# pc_healthypi_move_sensor_dual_v2.net
KiCad netlist of a schematic drawn in EAGLE
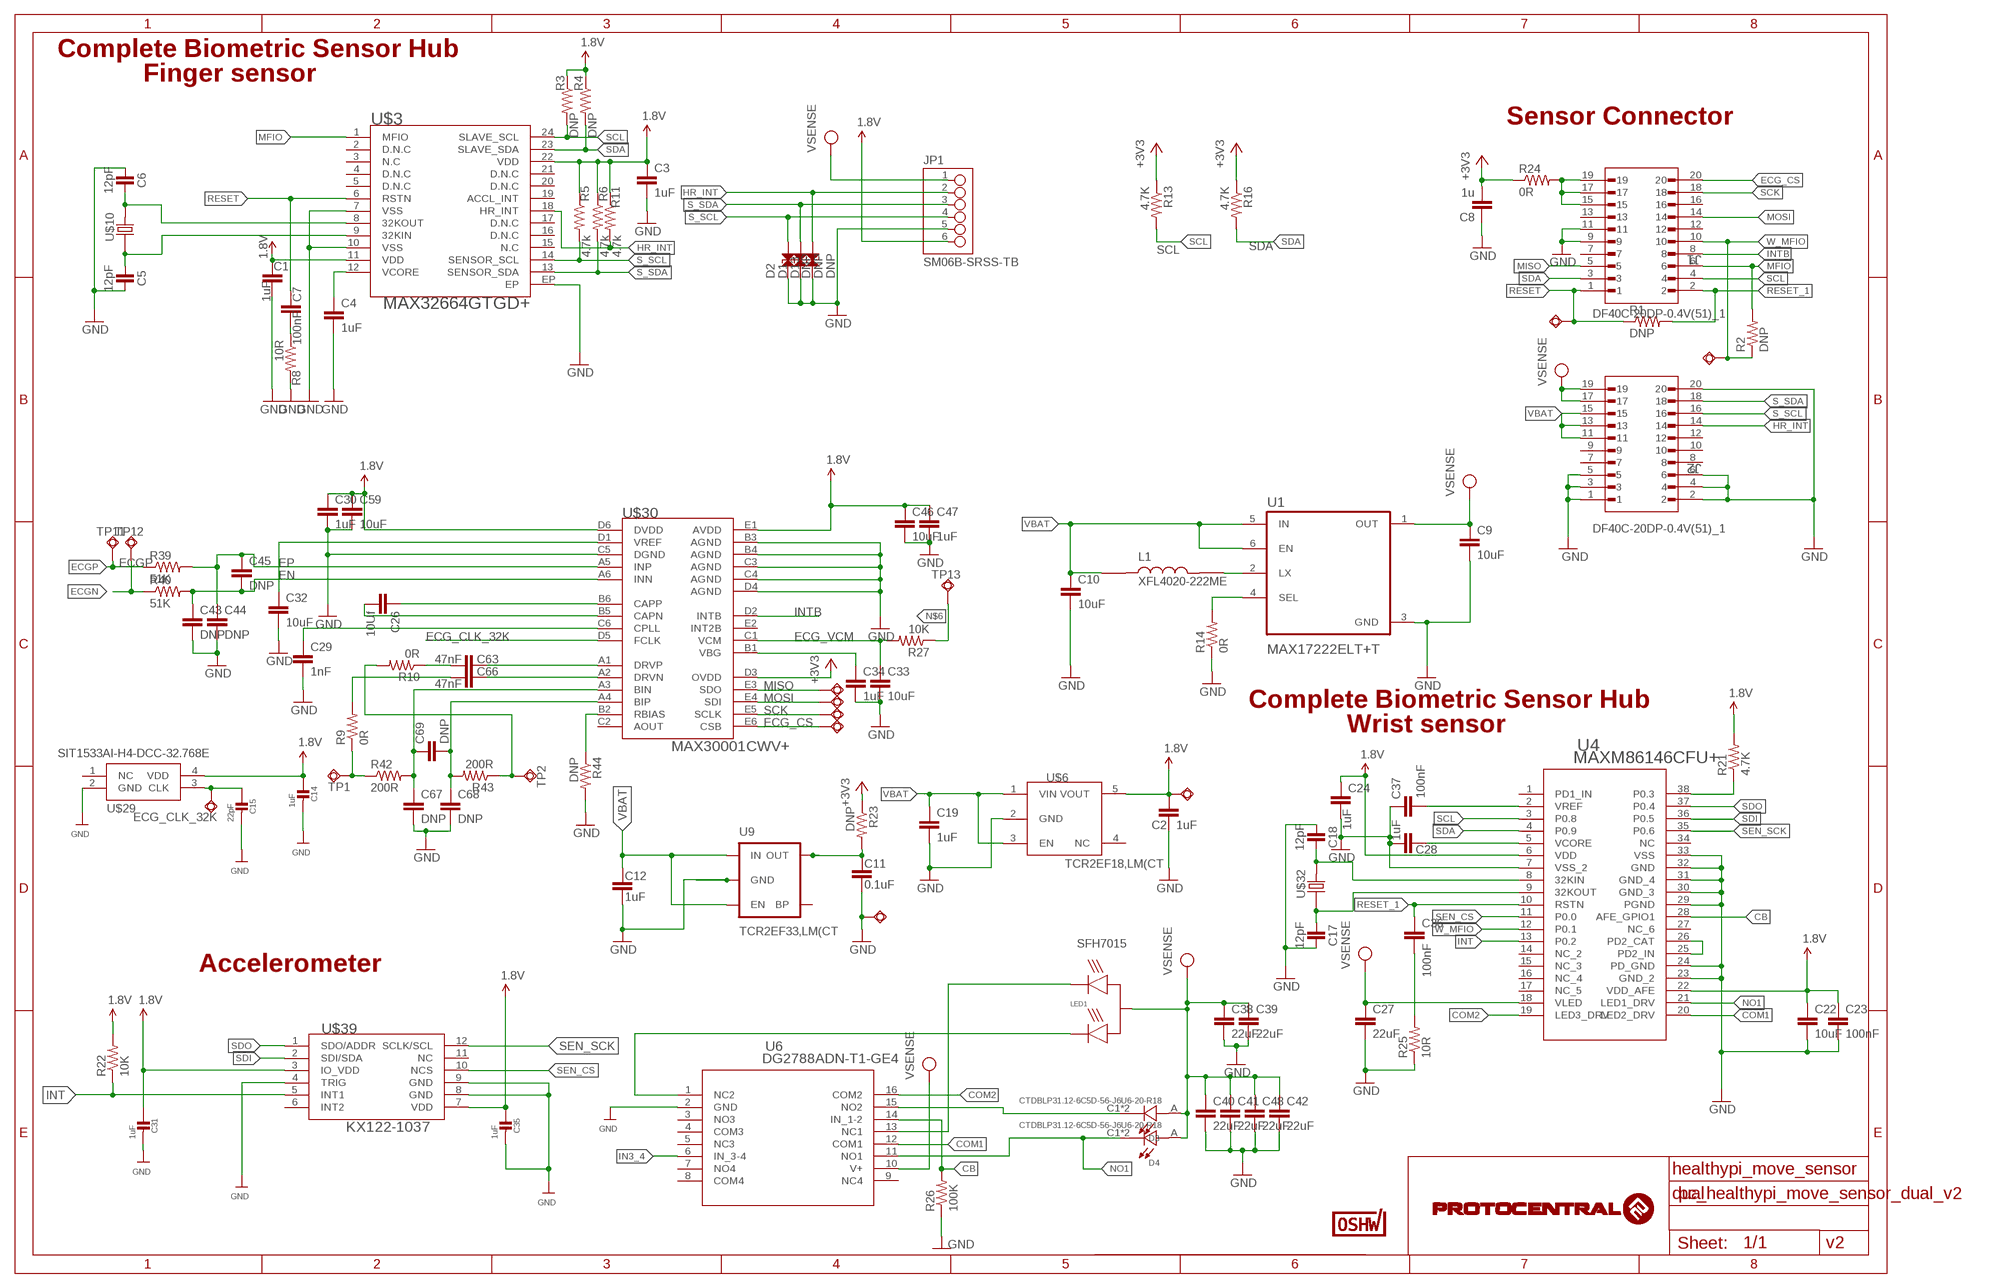
[diagram p0: schematic, sheet 1]

(export (version "E")
  (design (tool "Eeschema 10.0.6"))
  (components
    (comp (ref "C1")
      (value "1uF")
      (footprint "eagle-import:C0402")
      (libsource (lib "eagle-import") (part "C-EUC0402"))
    )
    (comp (ref "C2")
      (value "1uF")
      (footprint "eagle-import:C0402")
      (libsource (lib "eagle-import") (part "C-EUC0402"))
    )
    (comp (ref "C3")
      (value "1uF")
      (footprint "eagle-import:C0402")
      (libsource (lib "eagle-import") (part "C-EUC0402"))
    )
    (comp (ref "C4")
      (value "1uF")
      (footprint "eagle-import:C0402")
      (libsource (lib "eagle-import") (part "C-EUC0402"))
    )
    (comp (ref "C5")
      (value "12pF")
      (footprint "eagle-import:C0402")
      (libsource (lib "eagle-import") (part "CAPACITORS-0402"))
    )
    (comp (ref "C6")
      (value "12pF")
      (footprint "eagle-import:C0402")
      (libsource (lib "eagle-import") (part "CAPACITORS-0402"))
    )
    (comp (ref "C7")
      (value "100nF")
      (footprint "eagle-import:C0402")
      (libsource (lib "eagle-import") (part "C-EUC0402"))
    )
    (comp (ref "C8")
      (value "1u")
      (footprint "eagle-import:C0402")
      (libsource (lib "eagle-import") (part "C-EUC0402"))
    )
    (comp (ref "C9")
      (value "10uF")
      (footprint "eagle-import:C0402")
      (libsource (lib "eagle-import") (part "C-EUC0402"))
    )
    (comp (ref "C10")
      (value "10uF")
      (footprint "eagle-import:C0402")
      (libsource (lib "eagle-import") (part "C-EUC0402"))
    )
    (comp (ref "C11")
      (value "0.1uF")
      (footprint "eagle-import:0402")
      (libsource (lib "eagle-import") (part "0.1UF-0402-16V-10%"))
    )
    (comp (ref "C12")
      (value "1uF")
      (footprint "eagle-import:0402-TIGHT")
      (libsource (lib "eagle-import") (part "0.1UF-0402T-6.3V-10%-X7R"))
    )
    (comp (ref "C14")
      (value "1uF")
      (footprint "eagle-import:0402")
      (libsource (lib "eagle-import") (part "CAP_CERAMIC0402"))
    )
    (comp (ref "C15")
      (value "22pF")
      (footprint "eagle-import:0402")
      (libsource (lib "eagle-import") (part "CAP_CERAMIC0402"))
    )
    (comp (ref "C17")
      (value "12pF")
      (footprint "eagle-import:C0402")
      (libsource (lib "eagle-import") (part "CAPACITORS-0402"))
    )
    (comp (ref "C18")
      (value "12pF")
      (footprint "eagle-import:C0402")
      (libsource (lib "eagle-import") (part "CAPACITORS-0402"))
    )
    (comp (ref "C19")
      (value "1uF")
      (footprint "eagle-import:C0402")
      (libsource (lib "eagle-import") (part "C-EUC0402"))
    )
    (comp (ref "C22")
      (value "10uF")
      (footprint "eagle-import:C0402")
      (libsource (lib "eagle-import") (part "C-EUC0402"))
    )
    (comp (ref "C23")
      (value "100nF")
      (footprint "eagle-import:C0402")
      (libsource (lib "eagle-import") (part "C-EUC0402"))
    )
    (comp (ref "C24")
      (value "1uF")
      (footprint "eagle-import:C0402")
      (libsource (lib "eagle-import") (part "C-EUC0402"))
    )
    (comp (ref "C26")
      (value "10Uf")
      (footprint "eagle-import:C0402")
      (libsource (lib "eagle-import") (part "C-EUC0402"))
    )
    (comp (ref "C27")
      (value "22uF")
      (footprint "eagle-import:C0805")
      (libsource (lib "eagle-import") (part "C-EUC0805"))
    )
    (comp (ref "C28")
      (value "1uF")
      (footprint "eagle-import:C0402")
      (libsource (lib "eagle-import") (part "C-EUC0402"))
    )
    (comp (ref "C29")
      (value "1nF")
      (footprint "eagle-import:C0402")
      (libsource (lib "eagle-import") (part "C-EUC0402"))
    )
    (comp (ref "C30")
      (value "1uF")
      (footprint "eagle-import:C0402")
      (libsource (lib "eagle-import") (part "C-EUC0402"))
    )
    (comp (ref "C31")
      (value "1uF")
      (footprint "eagle-import:0402")
      (libsource (lib "eagle-import") (part "CAP_CERAMIC0402"))
    )
    (comp (ref "C32")
      (value "10uF")
      (footprint "eagle-import:C0402")
      (libsource (lib "eagle-import") (part "C-EUC0402"))
    )
    (comp (ref "C33")
      (value "10uF")
      (footprint "eagle-import:C0402")
      (libsource (lib "eagle-import") (part "C-EUC0402"))
    )
    (comp (ref "C34")
      (value "1uF")
      (footprint "eagle-import:C0402")
      (libsource (lib "eagle-import") (part "C-EUC0402"))
    )
    (comp (ref "C35")
      (value "1uF")
      (footprint "eagle-import:0402")
      (libsource (lib "eagle-import") (part "CAP_CERAMIC0402"))
    )
    (comp (ref "C36")
      (value "100nF")
      (footprint "eagle-import:C0402")
      (libsource (lib "eagle-import") (part "C-EUC0402"))
    )
    (comp (ref "C37")
      (value "100nF")
      (footprint "eagle-import:C0402")
      (libsource (lib "eagle-import") (part "C-EUC0402"))
    )
    (comp (ref "C38")
      (value "22uF")
      (footprint "eagle-import:C0805")
      (libsource (lib "eagle-import") (part "C-EUC0805"))
    )
    (comp (ref "C39")
      (value "22uF")
      (footprint "eagle-import:C0805")
      (libsource (lib "eagle-import") (part "C-EUC0805"))
    )
    (comp (ref "C40")
      (value "22uF")
      (footprint "eagle-import:C0805")
      (libsource (lib "eagle-import") (part "C-EUC0805"))
    )
    (comp (ref "C41")
      (value "22uF")
      (footprint "eagle-import:C0805")
      (libsource (lib "eagle-import") (part "C-EUC0805"))
    )
    (comp (ref "C42")
      (value "22uF")
      (footprint "eagle-import:C0805")
      (libsource (lib "eagle-import") (part "C-EUC0805"))
    )
    (comp (ref "C43")
      (value "DNP")
      (footprint "eagle-import:C0402")
      (libsource (lib "eagle-import") (part "C-EUC0402"))
    )
    (comp (ref "C44")
      (value "DNP")
      (footprint "eagle-import:C0402")
      (libsource (lib "eagle-import") (part "C-EUC0402"))
    )
    (comp (ref "C45")
      (value "DNP")
      (footprint "eagle-import:C0402")
      (libsource (lib "eagle-import") (part "C-EUC0402"))
    )
    (comp (ref "C46")
      (value "10uF")
      (footprint "eagle-import:C0402")
      (libsource (lib "eagle-import") (part "C-EUC0402"))
    )
    (comp (ref "C47")
      (value "1uF")
      (footprint "eagle-import:C0402")
      (libsource (lib "eagle-import") (part "C-EUC0402"))
    )
    (comp (ref "C48")
      (value "22uF")
      (footprint "eagle-import:C0805")
      (libsource (lib "eagle-import") (part "C-EUC0805"))
    )
    (comp (ref "C59")
      (value "10uF")
      (footprint "eagle-import:C0402")
      (libsource (lib "eagle-import") (part "C-EUC0402"))
    )
    (comp (ref "C63")
      (value "47nF")
      (footprint "eagle-import:C0402")
      (libsource (lib "eagle-import") (part "C-EUC0402"))
    )
    (comp (ref "C66")
      (value "47nF")
      (footprint "eagle-import:C0402")
      (libsource (lib "eagle-import") (part "C-EUC0402"))
    )
    (comp (ref "C67")
      (value "DNP")
      (footprint "eagle-import:C0402")
      (libsource (lib "eagle-import") (part "C-EUC0402"))
    )
    (comp (ref "C68")
      (value "DNP")
      (footprint "eagle-import:C0402")
      (libsource (lib "eagle-import") (part "C-EUC0402"))
    )
    (comp (ref "C69")
      (value "DNP")
      (footprint "eagle-import:C0402")
      (libsource (lib "eagle-import") (part "C-EUC0402"))
    )
    (comp (ref "D1")
      (value "DNP")
      (footprint "eagle-import:0402")
      (fields
        (field (name "DIGIKEY_PART") "PESD0402-140CT-ND")
        (field (name "MOUSE_PART") "650-PESD0402-140")
      )
      (libsource (lib "eagle-import") (part "PESD0402-0402"))
    )
    (comp (ref "D2")
      (value "DNP")
      (footprint "eagle-import:0402")
      (fields
        (field (name "DIGIKEY_PART") "PESD0402-140CT-ND")
        (field (name "MOUSE_PART") "650-PESD0402-140")
      )
      (libsource (lib "eagle-import") (part "PESD0402-0402"))
    )
    (comp (ref "D3")
      (value "CTDBLP31.12-6C5D-56-J6U6-20-R18")
      (footprint "eagle-import:LED_CTDBLP31.12-6C5D-56-J6U6-20-R18")
      (fields
        (field (name "MF") "OSRAM Opto Semiconductors")
        (field (name "MP") "CT DBLP31.12-6C5D-56-J6U6-20-R18")
      )
      (libsource (lib "eagle-import") (part "CTDBLP31.12-6C5D-56-J6U6-20-R18"))
    )
    (comp (ref "D4")
      (value "CTDBLP31.12-6C5D-56-J6U6-20-R18")
      (footprint "eagle-import:LED_CTDBLP31.12-6C5D-56-J6U6-20-R18")
      (fields
        (field (name "MF") "OSRAM Opto Semiconductors")
        (field (name "MP") "CT DBLP31.12-6C5D-56-J6U6-20-R18")
      )
      (libsource (lib "eagle-import") (part "CTDBLP31.12-6C5D-56-J6U6-20-R18"))
    )
    (comp (ref "D13")
      (value "DNP")
      (footprint "eagle-import:0402")
      (fields
        (field (name "DIGIKEY_PART") "PESD0402-140CT-ND")
        (field (name "MOUSE_PART") "650-PESD0402-140")
      )
      (libsource (lib "eagle-import") (part "PESD0402-0402"))
    )
    (comp (ref "J1")
      (value "DF40C-20DP-0.4V(51)_1")
      (footprint "eagle-import:HRS_DF40C-20DP-0.4V(51)")
      (fields (field (name "MANUFACTURER") "Hirose Electric"))
      (libsource (lib "eagle-import") (part "DF40C-20DP-0.4V(51)_1"))
    )
    (comp (ref "J2")
      (value "DF40C-20DP-0.4V(51)_1")
      (footprint "eagle-import:HRS_DF40C-20DP-0.4V(51)")
      (fields (field (name "MANUFACTURER") "Hirose Electric"))
      (libsource (lib "eagle-import") (part "DF40C-20DP-0.4V(51)_1"))
    )
    (comp (ref "JP1")
      (value "SM06B-SRSS-TB")
      (footprint "eagle-import:SM06B-SRSS-TB")
      (fields (field (name "MF") "JST Sales"))
      (libsource (lib "eagle-import") (part "SM06B-SRSS-TB"))
    )
    (comp (ref "L1")
      (value "XFL4020-222ME")
      (footprint "eagle-import:IND_XFL4020-222ME")
      (fields (field (name "MF") "Coilcraft"))
      (libsource (lib "eagle-import") (part "XFL4020-222ME"))
    )
    (comp (ref "LED1")
      (value "SFH7015")
      (footprint "eagle-import:SFH7015")
      (fields (field (name "MF") "OSRAM Opto Semiconductors") (field (name "MP") "SFH 7015"))
      (libsource (lib "eagle-import") (part "SFH7015"))
    )
    (comp (ref "R1")
      (value "DNP")
      (footprint "eagle-import:0402-RES")
      (libsource (lib "eagle-import") (part "RESISTOR0402-RES"))
    )
    (comp (ref "R2")
      (value "DNP")
      (footprint "eagle-import:0402-RES")
      (libsource (lib "eagle-import") (part "RESISTOR0402-RES"))
    )
    (comp (ref "R3")
      (value "DNP")
      (footprint "eagle-import:0402-RES")
      (libsource (lib "eagle-import") (part "RESISTOR0402-RES"))
    )
    (comp (ref "R4")
      (value "DNP")
      (footprint "eagle-import:0402-RES")
      (libsource (lib "eagle-import") (part "RESISTOR0402-RES"))
    )
    (comp (ref "R5")
      (value "4.7k")
      (footprint "eagle-import:0402-RES")
      (libsource (lib "eagle-import") (part "RESISTOR0402-RES"))
    )
    (comp (ref "R6")
      (value "4.7k")
      (footprint "eagle-import:0402-RES")
      (libsource (lib "eagle-import") (part "RESISTOR0402-RES"))
    )
    (comp (ref "R8")
      (value "10R")
      (footprint "eagle-import:0402-RES")
      (libsource (lib "eagle-import") (part "RESISTOR0402-RES"))
    )
    (comp (ref "R9")
      (value "0R")
      (footprint "eagle-import:0402-RES")
      (libsource (lib "eagle-import") (part "RESISTOR0402-RES"))
    )
    (comp (ref "R10")
      (value "0R")
      (footprint "eagle-import:0402-RES")
      (libsource (lib "eagle-import") (part "RESISTOR0402-RES"))
    )
    (comp (ref "R11")
      (value "4.7k")
      (footprint "eagle-import:0402-RES")
      (libsource (lib "eagle-import") (part "RESISTOR0402-RES"))
    )
    (comp (ref "R13")
      (value "4.7K")
      (footprint "eagle-import:0402-RES")
      (libsource (lib "eagle-import") (part "RESISTOR0402-RES"))
    )
    (comp (ref "R14")
      (value "0R")
      (footprint "eagle-import:R0402")
      (libsource (lib "eagle-import") (part "R-US_R0402"))
    )
    (comp (ref "R16")
      (value "4.7K")
      (footprint "eagle-import:0402-RES")
      (libsource (lib "eagle-import") (part "RESISTOR0402-RES"))
    )
    (comp (ref "R21")
      (value "4.7K")
      (footprint "eagle-import:R0402")
      (libsource (lib "eagle-import") (part "R-US_R0402"))
    )
    (comp (ref "R22")
      (value "10K")
      (footprint "eagle-import:0402-RES")
      (libsource (lib "eagle-import") (part "RESISTOR0402-RES"))
    )
    (comp (ref "R23")
      (value "DNP")
      (footprint "eagle-import:0402-RES")
      (libsource (lib "eagle-import") (part "RESISTOR0402-RES"))
    )
    (comp (ref "R24")
      (value "0R")
      (footprint "eagle-import:0402-RES")
      (libsource (lib "eagle-import") (part "RESISTOR0402-RES"))
    )
    (comp (ref "R25")
      (value "10R")
      (footprint "eagle-import:R0402")
      (libsource (lib "eagle-import") (part "R-US_R0402"))
    )
    (comp (ref "R26")
      (value "100K")
      (footprint "eagle-import:R0402")
      (libsource (lib "eagle-import") (part "R-US_R0402"))
    )
    (comp (ref "R27")
      (value "10K")
      (footprint "eagle-import:R0402")
      (libsource (lib "eagle-import") (part "R-US_R0402"))
    )
    (comp (ref "R39")
      (value "51K")
      (footprint "eagle-import:0402-RES")
      (libsource (lib "eagle-import") (part "RESISTOR0402-RES"))
    )
    (comp (ref "R40")
      (value "51K")
      (footprint "eagle-import:0402-RES")
      (libsource (lib "eagle-import") (part "RESISTOR0402-RES"))
    )
    (comp (ref "R42")
      (value "200R")
      (footprint "eagle-import:0402-RES")
      (libsource (lib "eagle-import") (part "RESISTOR0402-RES"))
    )
    (comp (ref "R43")
      (value "200R")
      (footprint "eagle-import:0402-RES")
      (libsource (lib "eagle-import") (part "RESISTOR0402-RES"))
    )
    (comp (ref "R44")
      (value "DNP")
      (footprint "eagle-import:0402-RES")
      (libsource (lib "eagle-import") (part "RESISTOR0402-RES"))
    )
    (comp (ref "SWIO1")
      (value "TPSQTP11R")
      (footprint "eagle-import:TP11R")
      (libsource (lib "eagle-import") (part "TPSQTP11R"))
    )
    (comp (ref "SWIO2")
      (value "TPSQTP11R")
      (footprint "eagle-import:TP11R")
      (libsource (lib "eagle-import") (part "TPSQTP11R"))
    )
    (comp (ref "SWIO3")
      (value "TPSQTP11R")
      (footprint "eagle-import:TP11R")
      (libsource (lib "eagle-import") (part "TPSQTP11R"))
    )
    (comp (ref "SWIO4")
      (value "TPSQTP11R")
      (footprint "eagle-import:TP11R")
      (libsource (lib "eagle-import") (part "TPSQTP11R"))
    )
    (comp (ref "SWIO5")
      (value "TPSQTP11R")
      (footprint "eagle-import:TP11R")
      (libsource (lib "eagle-import") (part "TPSQTP11R"))
    )
    (comp (ref "SWIO6")
      (value "TPSQTP11R")
      (footprint "eagle-import:TP11R")
      (libsource (lib "eagle-import") (part "TPSQTP11R"))
    )
    (comp (ref "SWIO7")
      (value "TPSQTP11R")
      (footprint "eagle-import:TP11R")
      (libsource (lib "eagle-import") (part "TPSQTP11R"))
    )
    (comp (ref "SWIO8")
      (value "TPSQTP11R")
      (footprint "eagle-import:TP11R")
      (libsource (lib "eagle-import") (part "TPSQTP11R"))
    )
    (comp (ref "SWIO9")
      (value "TPSQTP11R")
      (footprint "eagle-import:TP11R")
      (libsource (lib "eagle-import") (part "TPSQTP11R"))
    )
    (comp (ref "TP1")
      (value "TPSQTP20SQ")
      (footprint "eagle-import:TP20SQ")
      (libsource (lib "eagle-import") (part "TPSQTP20SQ"))
    )
    (comp (ref "TP2")
      (value "TPSQTP20SQ")
      (footprint "eagle-import:TP20SQ")
      (libsource (lib "eagle-import") (part "TPSQTP20SQ"))
    )
    (comp (ref "TP11")
      (value "TPSQTP20SQ")
      (footprint "eagle-import:TP20SQ")
      (libsource (lib "eagle-import") (part "TPSQTP20SQ"))
    )
    (comp (ref "TP12")
      (value "TPSQTP20SQ")
      (footprint "eagle-import:TP20SQ")
      (libsource (lib "eagle-import") (part "TPSQTP20SQ"))
    )
    (comp (ref "TP13")
      (value "TPSQTP20SQ")
      (footprint "eagle-import:TP20SQ")
      (libsource (lib "eagle-import") (part "TPSQTP20SQ"))
    )
    (comp (ref "U$3")
      (value "MAX32664GTGD+")
      (footprint "eagle-import:TQFN-24L")
      (libsource (lib "eagle-import") (part "MAX32664GTGA+"))
    )
    (comp (ref "U$6")
      (value "TCR2EF18,LM(CT")
      (footprint "eagle-import:SOT95P285X140-5N")
      (libsource (lib "eagle-import") (part "AP7354D-18W5-7"))
    )
    (comp (ref "U$10")
      (value "520-327-12.5-34B(32.768KHZ)")
      (footprint "eagle-import:ECX-31B")
      (libsource (lib "eagle-import") (part "ECS-X-34B"))
    )
    (comp (ref "U$29")
      (value "SIT1533AI-H4-DCC-32.768E")
      (footprint "eagle-import:SIT1533")
      (libsource (lib "eagle-import") (part "SIT1533AI-H4-DCC-32.768E"))
    )
    (comp (ref "U$30")
      (value "MAX30001CWV+")
      (footprint "eagle-import:30WLP")
      (libsource (lib "eagle-import") (part "MAX30001CWV+"))
    )
    (comp (ref "U$32")
      (value "520-327-12.5-34B(32.768KHZ)")
      (footprint "eagle-import:ECX-31B")
      (libsource (lib "eagle-import") (part "ECS-X-34B"))
    )
    (comp (ref "U$39")
      (value "KX122-1037")
      (footprint "eagle-import:KIONIX_KXTJ3-1057")
      (libsource (lib "eagle-import") (part "KX122-1037"))
    )
    (comp (ref "U$48")
      (value "CERT-SMALL")
      (footprint "eagle-import:CERT-SMALL-SILK")
      (libsource (lib "eagle-import") (part "CERT-SMALL"))
    )
    (comp (ref "U1")
      (value "MAX17222ELT+T")
      (footprint "eagle-import:SON65P200X200X80-6N")
      (fields (field (name "MF") "Analog Devices"))
      (libsource (lib "eagle-import") (part "MAX17222ELT+T"))
    )
    (comp (ref "U4")
      (value "MAXM86146CFU+")
      (footprint "eagle-import:21-100323A_90-100112A_MXM")
      (fields (field (name "COPYRIGHT") "Copyright (C) 2023 Ultra Librarian. All rights reserved."))
      (libsource (lib "eagle-import") (part "MAXM86146CFU+"))
    )
    (comp (ref "U6")
      (value "DG2788ADN-T1-GE4")
      (footprint "eagle-import:MINIQFN-16_VIS")
      (fields (field (name "COPYRIGHT") "Copyright (C) 2023 Ultra Librarian. All rights reserved."))
      (libsource (lib "eagle-import") (part "DG2788ADN-T1-GE4"))
    )
    (comp (ref "U9")
      (value "TCR2EF33,LM(CT")
      (footprint "eagle-import:SOT23-5")
      (libsource (lib "eagle-import") (part "V_REG_LDOSMD"))
    )
  )
  (nets
    (net (code "1") (name "+3V3") (class "Default")
      (node (ref "C8") (pin "2") (pinfunction "2_2") (pintype "passive"))
      (node (ref "R13") (pin "1") (pinfunction "1_1") (pintype "passive"))
      (node (ref "R16") (pin "1") (pinfunction "1_1") (pintype "passive"))
      (node (ref "R23") (pin "1") (pinfunction "1_1") (pintype "passive"))
      (node (ref "R24") (pin "1") (pinfunction "1_1") (pintype "passive"))
      (node (ref "U$30") (pin "D3") (pinfunction "OVDD_D3") (pintype "bidirectional"))
    )
    (net (code "2") (name "/ECG_CLK_32K") (class "Default")
      (node (ref "C15") (pin "1") (pinfunction "P$1_1") (pintype "passive"))
      (node (ref "SWIO1") (pin "TP") (pinfunction "TP_TP") (pintype "input"))
      (node (ref "U$29") (pin "3") (pinfunction "CLK_3") (pintype "bidirectional"))
      (node (ref "U$30") (pin "D5") (pinfunction "FCLK_D5") (pintype "bidirectional"))
    )
    (net (code "3") (name "/ECG_VCM") (class "Default")
      (node (ref "C33") (pin "1") (pinfunction "1_1") (pintype "passive"))
      (node (ref "R27") (pin "2") (pinfunction "2_2") (pintype "passive"))
      (node (ref "U$30") (pin "C1") (pinfunction "VCM_C1") (pintype "bidirectional"))
    )
    (net (code "4") (name "/EN") (class "Default")
      (node (ref "C43") (pin "1") (pinfunction "1_1") (pintype "passive"))
      (node (ref "C45") (pin "2") (pinfunction "2_2") (pintype "passive"))
      (node (ref "R40") (pin "2") (pinfunction "2_2") (pintype "passive"))
      (node (ref "U$30") (pin "A6") (pinfunction "INN_A6") (pintype "bidirectional"))
    )
    (net (code "5") (name "/EP") (class "Default")
      (node (ref "C44") (pin "1") (pinfunction "1_1") (pintype "passive"))
      (node (ref "C45") (pin "1") (pinfunction "1_1") (pintype "passive"))
      (node (ref "R39") (pin "2") (pinfunction "2_2") (pintype "passive"))
      (node (ref "U$30") (pin "A5") (pinfunction "INP_A5") (pintype "bidirectional"))
    )
    (net (code "6") (name "1.8V") (class "Default")
      (node (ref "C1") (pin "1") (pinfunction "1_1") (pintype "passive"))
      (node (ref "C14") (pin "1") (pinfunction "P$1_1") (pintype "passive"))
      (node (ref "C2") (pin "1") (pinfunction "1_1") (pintype "passive"))
      (node (ref "C22") (pin "1") (pinfunction "1_1") (pintype "passive"))
      (node (ref "C23") (pin "1") (pinfunction "1_1") (pintype "passive"))
      (node (ref "C24") (pin "1") (pinfunction "1_1") (pintype "passive"))
      (node (ref "C3") (pin "1") (pinfunction "1_1") (pintype "passive"))
      (node (ref "C30") (pin "1") (pinfunction "1_1") (pintype "passive"))
      (node (ref "C31") (pin "1") (pinfunction "P$1_1") (pintype "passive"))
      (node (ref "C35") (pin "1") (pinfunction "P$1_1") (pintype "passive"))
      (node (ref "C46") (pin "1") (pinfunction "1_1") (pintype "passive"))
      (node (ref "C47") (pin "1") (pinfunction "1_1") (pintype "passive"))
      (node (ref "C59") (pin "1") (pinfunction "1_1") (pintype "passive"))
      (node (ref "JP1") (pin "6") (pinfunction "P$6_6") (pintype "bidirectional"))
      (node (ref "R11") (pin "1") (pinfunction "1_1") (pintype "passive"))
      (node (ref "R21") (pin "2") (pinfunction "2_2") (pintype "passive"))
      (node (ref "R22") (pin "2") (pinfunction "2_2") (pintype "passive"))
      (node (ref "R3") (pin "1") (pinfunction "1_1") (pintype "passive"))
      (node (ref "R4") (pin "1") (pinfunction "1_1") (pintype "passive"))
      (node (ref "R5") (pin "1") (pinfunction "1_1") (pintype "passive"))
      (node (ref "R6") (pin "1") (pinfunction "1_1") (pintype "passive"))
      (node (ref "SWIO5") (pin "TP") (pinfunction "TP_TP") (pintype "input"))
      (node (ref "U$29") (pin "4") (pinfunction "VDD_4") (pintype "bidirectional"))
      (node (ref "U$3") (pin "11") (pinfunction "VDD_11") (pintype "bidirectional"))
      (node (ref "U$3") (pin "22") (pinfunction "VDD_22") (pintype "bidirectional"))
      (node (ref "U$30") (pin "D6") (pinfunction "DVDD_D6") (pintype "bidirectional"))
      (node (ref "U$30") (pin "E1") (pinfunction "AVDD_E1") (pintype "bidirectional"))
      (node (ref "U$39") (pin "3") (pinfunction "IO_VDD_3") (pintype "bidirectional"))
      (node (ref "U$39") (pin "7") (pinfunction "VDD_7") (pintype "bidirectional"))
      (node (ref "U$6") (pin "5") (pinfunction "VOUT_5") (pintype "bidirectional"))
      (node (ref "U4") (pin "22") (pinfunction "VDD_AFE_22") (pintype "input"))
      (node (ref "U4") (pin "6") (pinfunction "VDD_6") (pintype "power_in"))
    )
    (net (code "7") (name "CB") (class "Default")
      (node (ref "R26") (pin "2") (pinfunction "2_2") (pintype "passive"))
      (node (ref "U4") (pin "28") (pinfunction "AFE_GPIO1_28") (pintype "bidirectional"))
      (node (ref "U6") (pin "14") (pinfunction "IN_1-2_14") (pintype "bidirectional"))
    )
    (net (code "8") (name "COM1") (class "Default")
      (node (ref "U4") (pin "20") (pinfunction "LED2_DRV_20") (pintype "output"))
      (node (ref "U6") (pin "12") (pinfunction "COM1_12") (pintype "bidirectional"))
    )
    (net (code "9") (name "COM2") (class "Default")
      (node (ref "U4") (pin "19") (pinfunction "LED3_DRV_19") (pintype "output"))
      (node (ref "U6") (pin "16") (pinfunction "COM2_16") (pintype "bidirectional"))
    )
    (net (code "10") (name "ECGN") (class "Default")
      (node (ref "R40") (pin "1") (pinfunction "1_1") (pintype "passive"))
      (node (ref "TP12") (pin "TP") (pinfunction "TP_TP") (pintype "input"))
    )
    (net (code "11") (name "ECGP") (class "Default")
      (node (ref "R39") (pin "1") (pinfunction "1_1") (pintype "passive"))
      (node (ref "TP11") (pin "TP") (pinfunction "TP_TP") (pintype "input"))
    )
    (net (code "12") (name "ECG_CS") (class "Default")
      (node (ref "J1") (pin "20") (pinfunction "20_20") (pintype "passive"))
      (node (ref "SWIO7") (pin "TP") (pinfunction "TP_TP") (pintype "input"))
      (node (ref "U$30") (pin "E6") (pinfunction "CSB_E6") (pintype "bidirectional"))
    )
    (net (code "13") (name "GND") (class "Default")
      (node (ref "C1") (pin "2") (pinfunction "2_2") (pintype "passive"))
      (node (ref "C10") (pin "2") (pinfunction "2_2") (pintype "passive"))
      (node (ref "C11") (pin "2") (pinfunction "2_2") (pintype "passive"))
      (node (ref "C12") (pin "2") (pinfunction "2_2") (pintype "passive"))
      (node (ref "C14") (pin "2") (pinfunction "P$2_2") (pintype "passive"))
      (node (ref "C15") (pin "2") (pinfunction "P$2_2") (pintype "passive"))
      (node (ref "C17") (pin "2") (pinfunction "2_2") (pintype "passive"))
      (node (ref "C18") (pin "1") (pinfunction "1_1") (pintype "passive"))
      (node (ref "C19") (pin "2") (pinfunction "2_2") (pintype "passive"))
      (node (ref "C2") (pin "2") (pinfunction "2_2") (pintype "passive"))
      (node (ref "C22") (pin "2") (pinfunction "2_2") (pintype "passive"))
      (node (ref "C23") (pin "2") (pinfunction "2_2") (pintype "passive"))
      (node (ref "C24") (pin "2") (pinfunction "2_2") (pintype "passive"))
      (node (ref "C27") (pin "2") (pinfunction "2_2") (pintype "passive"))
      (node (ref "C28") (pin "2") (pinfunction "2_2") (pintype "passive"))
      (node (ref "C29") (pin "2") (pinfunction "2_2") (pintype "passive"))
      (node (ref "C3") (pin "2") (pinfunction "2_2") (pintype "passive"))
      (node (ref "C30") (pin "2") (pinfunction "2_2") (pintype "passive"))
      (node (ref "C31") (pin "2") (pinfunction "P$2_2") (pintype "passive"))
      (node (ref "C32") (pin "2") (pinfunction "2_2") (pintype "passive"))
      (node (ref "C33") (pin "2") (pinfunction "2_2") (pintype "passive"))
      (node (ref "C34") (pin "2") (pinfunction "2_2") (pintype "passive"))
      (node (ref "C35") (pin "2") (pinfunction "P$2_2") (pintype "passive"))
      (node (ref "C37") (pin "1") (pinfunction "1_1") (pintype "passive"))
      (node (ref "C38") (pin "2") (pinfunction "2_2") (pintype "passive"))
      (node (ref "C39") (pin "2") (pinfunction "2_2") (pintype "passive"))
      (node (ref "C4") (pin "2") (pinfunction "2_2") (pintype "passive"))
      (node (ref "C40") (pin "2") (pinfunction "2_2") (pintype "passive"))
      (node (ref "C41") (pin "2") (pinfunction "2_2") (pintype "passive"))
      (node (ref "C42") (pin "2") (pinfunction "2_2") (pintype "passive"))
      (node (ref "C43") (pin "2") (pinfunction "2_2") (pintype "passive"))
      (node (ref "C44") (pin "2") (pinfunction "2_2") (pintype "passive"))
      (node (ref "C46") (pin "2") (pinfunction "2_2") (pintype "passive"))
      (node (ref "C47") (pin "2") (pinfunction "2_2") (pintype "passive"))
      (node (ref "C48") (pin "2") (pinfunction "2_2") (pintype "passive"))
      (node (ref "C5") (pin "2") (pinfunction "2_2") (pintype "passive"))
      (node (ref "C59") (pin "2") (pinfunction "2_2") (pintype "passive"))
      (node (ref "C6") (pin "1") (pinfunction "1_1") (pintype "passive"))
      (node (ref "C67") (pin "2") (pinfunction "2_2") (pintype "passive"))
      (node (ref "C68") (pin "2") (pinfunction "2_2") (pintype "passive"))
      (node (ref "C8") (pin "1") (pinfunction "1_1") (pintype "passive"))
      (node (ref "C9") (pin "2") (pinfunction "2_2") (pintype "passive"))
      (node (ref "D1") (pin "1") (pinfunction "1_1") (pintype "bidirectional"))
      (node (ref "D13") (pin "1") (pinfunction "1_1") (pintype "bidirectional"))
      (node (ref "D2") (pin "1") (pinfunction "1_1") (pintype "bidirectional"))
      (node (ref "J1") (pin "11") (pinfunction "11_11") (pintype "passive"))
      (node (ref "J1") (pin "9") (pinfunction "9_9") (pintype "passive"))
      (node (ref "J2") (pin "1") (pinfunction "1_1") (pintype "passive"))
      (node (ref "J2") (pin "2") (pinfunction "2_2") (pintype "passive"))
      (node (ref "J2") (pin "20") (pinfunction "20_20") (pintype "passive"))
      (node (ref "J2") (pin "3") (pinfunction "3_3") (pintype "passive"))
      (node (ref "J2") (pin "4") (pinfunction "4_4") (pintype "passive"))
      (node (ref "J2") (pin "5") (pinfunction "5_5") (pintype "passive"))
      (node (ref "J2") (pin "6") (pinfunction "6_6") (pintype "passive"))
      (node (ref "JP1") (pin "5") (pinfunction "P$5_5") (pintype "bidirectional"))
      (node (ref "R14") (pin "1") (pinfunction "1_1") (pintype "passive"))
      (node (ref "R25") (pin "1") (pinfunction "1_1") (pintype "passive"))
      (node (ref "R26") (pin "1") (pinfunction "1_1") (pintype "passive"))
      (node (ref "R44") (pin "2") (pinfunction "2_2") (pintype "passive"))
      (node (ref "R8") (pin "2") (pinfunction "2_2") (pintype "passive"))
      (node (ref "SWIO6") (pin "TP") (pinfunction "TP_TP") (pintype "input"))
      (node (ref "U$29") (pin "2") (pinfunction "GND_2") (pintype "bidirectional"))
      (node (ref "U$3") (pin "10") (pinfunction "VSS_10") (pintype "bidirectional"))
      (node (ref "U$3") (pin "7") (pinfunction "VSS_7") (pintype "bidirectional"))
      (node (ref "U$3") (pin "EP") (pinfunction "EP_EP") (pintype "bidirectional"))
      (node (ref "U$30") (pin "B3") (pinfunction "AGND_B3") (pintype "bidirectional"))
      (node (ref "U$30") (pin "B4") (pinfunction "AGND_B4") (pintype "bidirectional"))
      (node (ref "U$30") (pin "C3") (pinfunction "AGND_C3") (pintype "bidirectional"))
      (node (ref "U$30") (pin "C4") (pinfunction "AGND_C4") (pintype "bidirectional"))
      (node (ref "U$30") (pin "C5") (pinfunction "DGND_C5") (pintype "bidirectional"))
      (node (ref "U$30") (pin "D4") (pinfunction "AGND_D4") (pintype "bidirectional"))
      (node (ref "U$39") (pin "4") (pinfunction "TRIG_4") (pintype "bidirectional"))
      (node (ref "U$39") (pin "8") (pinfunction "GND_8") (pintype "bidirectional"))
      (node (ref "U$39") (pin "9") (pinfunction "GND_9") (pintype "bidirectional"))
      (node (ref "U$6") (pin "2") (pinfunction "GND_2") (pintype "bidirectional"))
      (node (ref "U1") (pin "3") (pinfunction "GND_3") (pintype "power_in"))
      (node (ref "U4") (pin "23") (pinfunction "GND_2_23") (pintype "power_in"))
      (node (ref "U4") (pin "24") (pinfunction "PD_GND_24") (pintype "passive"))
      (node (ref "U4") (pin "29") (pinfunction "PGND_29") (pintype "power_in"))
      (node (ref "U4") (pin "30") (pinfunction "GND_3_30") (pintype "power_in"))
      (node (ref "U4") (pin "31") (pinfunction "GND_4_31") (pintype "power_in"))
      (node (ref "U4") (pin "32") (pinfunction "GND_32") (pintype "power_in"))
      (node (ref "U4") (pin "33") (pinfunction "VSS_33") (pintype "power_in"))
      (node (ref "U4") (pin "7") (pinfunction "VSS_2_7") (pintype "power_in"))
      (node (ref "U6") (pin "2") (pinfunction "GND_2") (pintype "passive"))
      (node (ref "U9") (pin "2") (pinfunction "GND_2") (pintype "input"))
    )
    (net (code "14") (name "HR_INT") (class "Default")
      (node (ref "D13") (pin "2") (pinfunction "2_2") (pintype "bidirectional"))
      (node (ref "J2") (pin "14") (pinfunction "14_14") (pintype "passive"))
      (node (ref "JP1") (pin "2") (pinfunction "P$2_2") (pintype "bidirectional"))
      (node (ref "R11") (pin "2") (pinfunction "2_2") (pintype "passive"))
      (node (ref "U$3") (pin "18") (pinfunction "HR_INT_18") (pintype "bidirectional"))
    )
    (net (code "15") (name "IN3_4") (class "Default")
      (node (ref "U6") (pin "6") (pinfunction "IN_3-4_6") (pintype "bidirectional"))
    )
    (net (code "16") (name "INT") (class "Default")
      (node (ref "R22") (pin "1") (pinfunction "1_1") (pintype "passive"))
      (node (ref "U$39") (pin "5") (pinfunction "INT1_5") (pintype "bidirectional"))
      (node (ref "U4") (pin "13") (pinfunction "P0.2_13") (pintype "passive"))
    )
    (net (code "17") (name "INTB") (class "Default")
      (node (ref "J1") (pin "8") (pinfunction "8_8") (pintype "passive"))
      (node (ref "U$30") (pin "D2") (pinfunction "INTB_D2") (pintype "bidirectional"))
    )
    (net (code "18") (name "MFIO") (class "Default")
      (node (ref "J1") (pin "6") (pinfunction "6_6") (pintype "passive"))
      (node (ref "R2") (pin "2") (pinfunction "2_2") (pintype "passive"))
      (node (ref "U$3") (pin "1") (pinfunction "MFIO_1") (pintype "bidirectional"))
    )
    (net (code "19") (name "MISO") (class "Default")
      (node (ref "J1") (pin "5") (pinfunction "5_5") (pintype "passive"))
      (node (ref "SWIO2") (pin "TP") (pinfunction "TP_TP") (pintype "input"))
      (node (ref "U$30") (pin "E3") (pinfunction "SDO_E3") (pintype "bidirectional"))
    )
    (net (code "20") (name "MOSI") (class "Default")
      (node (ref "J1") (pin "14") (pinfunction "14_14") (pintype "passive"))
      (node (ref "SWIO3") (pin "TP") (pinfunction "TP_TP") (pintype "input"))
      (node (ref "U$30") (pin "E4") (pinfunction "SDI_E4") (pintype "bidirectional"))
    )
    (net (code "21") (name "N$6") (class "Default")
      (node (ref "R27") (pin "1") (pinfunction "1_1") (pintype "passive"))
      (node (ref "TP13") (pin "TP") (pinfunction "TP_TP") (pintype "input"))
    )
    (net (code "22") (name "NO1") (class "Default")
      (node (ref "D4") (pin "C1") (pinfunction "C_C1") (pintype "passive"))
      (node (ref "D4") (pin "C2") (pinfunction "C_C2") (pintype "passive"))
      (node (ref "U4") (pin "21") (pinfunction "LED1_DRV_21") (pintype "output"))
      (node (ref "U6") (pin "11") (pinfunction "NO1_11") (pintype "bidirectional"))
    )
    (net (code "23") (name "Net-(C7-Pad2)") (class "Default")
      (node (ref "C7") (pin "2") (pinfunction "2_2") (pintype "passive"))
      (node (ref "R8") (pin "1") (pinfunction "1_1") (pintype "passive"))
    )
    (net (code "24") (name "Net-(C36-Pad2)") (class "Default")
      (node (ref "C36") (pin "2") (pinfunction "2_2") (pintype "passive"))
      (node (ref "R25") (pin "2") (pinfunction "2_2") (pintype "passive"))
    )
    (net (code "25") (name "Net-(C63-Pad1)") (class "Default")
      (node (ref "C63") (pin "1") (pinfunction "1_1") (pintype "passive"))
      (node (ref "R10") (pin "1") (pinfunction "1_1") (pintype "passive"))
    )
    (net (code "26") (name "Net-(C66-Pad1)") (class "Default")
      (node (ref "C66") (pin "1") (pinfunction "1_1") (pintype "passive"))
      (node (ref "R9") (pin "2") (pinfunction "2_2") (pintype "passive"))
    )
    (net (code "27") (name "Net-(J1-Pad15)") (class "Default")
      (node (ref "J1") (pin "15") (pinfunction "15_15") (pintype "passive"))
      (node (ref "J1") (pin "17") (pinfunction "17_17") (pintype "passive"))
      (node (ref "J1") (pin "19") (pinfunction "19_19") (pintype "passive"))
      (node (ref "R24") (pin "2") (pinfunction "2_2") (pintype "passive"))
    )
    (net (code "28") (name "Net-(LED1-IRC)") (class "Default")
      (node (ref "LED1") (pin "4") (pinfunction "IRC_4") (pintype "passive"))
      (node (ref "U6") (pin "13") (pinfunction "NC1_13") (pintype "bidirectional"))
    )
    (net (code "29") (name "Net-(LED1-RC)") (class "Default")
      (node (ref "LED1") (pin "2") (pinfunction "RC_2") (pintype "passive"))
      (node (ref "U6") (pin "1") (pinfunction "NC2_1") (pintype "bidirectional"))
    )
    (net (code "30") (name "Net-(R10-Pad2)") (class "Default")
      (node (ref "R10") (pin "2") (pinfunction "2_2") (pintype "passive"))
      (node (ref "R43") (pin "1") (pinfunction "1_1") (pintype "passive"))
      (node (ref "TP2") (pin "TP") (pinfunction "TP_TP") (pintype "input"))
    )
    (net (code "31") (name "Net-(R42-Pad1)") (class "Default")
      (node (ref "R42") (pin "1") (pinfunction "1_1") (pintype "passive"))
      (node (ref "R9") (pin "1") (pinfunction "1_1") (pintype "passive"))
      (node (ref "TP1") (pin "TP") (pinfunction "TP_TP") (pintype "input"))
    )
    (net (code "32") (name "Net-(U$3-VCORE)") (class "Default")
      (node (ref "C4") (pin "1") (pinfunction "1_1") (pintype "passive"))
      (node (ref "U$3") (pin "12") (pinfunction "VCORE_12") (pintype "bidirectional"))
    )
    (net (code "33") (name "Net-(U$10-1)") (class "Default")
      (node (ref "C5") (pin "1") (pinfunction "1_1") (pintype "passive"))
      (node (ref "U$10") (pin "P$1") (pinfunction "1_P$1") (pintype "passive"))
      (node (ref "U$3") (pin "9") (pinfunction "32KIN_9") (pintype "bidirectional"))
    )
    (net (code "34") (name "Net-(U$10-2)") (class "Default")
      (node (ref "C6") (pin "2") (pinfunction "2_2") (pintype "passive"))
      (node (ref "U$10") (pin "P$2") (pinfunction "2_P$2") (pintype "passive"))
      (node (ref "U$3") (pin "8") (pinfunction "32KOUT_8") (pintype "bidirectional"))
    )
    (net (code "35") (name "Net-(U$30-BIN)") (class "Default")
      (node (ref "C67") (pin "1") (pinfunction "1_1") (pintype "passive"))
      (node (ref "C69") (pin "1") (pinfunction "1_1") (pintype "passive"))
      (node (ref "R42") (pin "2") (pinfunction "2_2") (pintype "passive"))
      (node (ref "U$30") (pin "A3") (pinfunction "BIN_A3") (pintype "bidirectional"))
    )
    (net (code "36") (name "Net-(U$30-BIP)") (class "Default")
      (node (ref "C68") (pin "1") (pinfunction "1_1") (pintype "passive"))
      (node (ref "C69") (pin "2") (pinfunction "2_2") (pintype "passive"))
      (node (ref "R43") (pin "2") (pinfunction "2_2") (pintype "passive"))
      (node (ref "U$30") (pin "A4") (pinfunction "BIP_A4") (pintype "bidirectional"))
    )
    (net (code "37") (name "Net-(U$30-CAPN)") (class "Default")
      (node (ref "C26") (pin "2") (pinfunction "2_2") (pintype "passive"))
      (node (ref "U$30") (pin "B5") (pinfunction "CAPN_B5") (pintype "bidirectional"))
    )
    (net (code "38") (name "Net-(U$30-CAPP)") (class "Default")
      (node (ref "C26") (pin "1") (pinfunction "1_1") (pintype "passive"))
      (node (ref "U$30") (pin "B6") (pinfunction "CAPP_B6") (pintype "bidirectional"))
    )
    (net (code "39") (name "Net-(U$30-CPLL)") (class "Default")
      (node (ref "C29") (pin "1") (pinfunction "1_1") (pintype "passive"))
      (node (ref "U$30") (pin "C6") (pinfunction "CPLL_C6") (pintype "bidirectional"))
    )
    (net (code "40") (name "Net-(U$30-DRVN)") (class "Default")
      (node (ref "C66") (pin "2") (pinfunction "2_2") (pintype "passive"))
      (node (ref "U$30") (pin "A2") (pinfunction "DRVN_A2") (pintype "bidirectional"))
    )
    (net (code "41") (name "Net-(U$30-DRVP)") (class "Default")
      (node (ref "C63") (pin "2") (pinfunction "2_2") (pintype "passive"))
      (node (ref "U$30") (pin "A1") (pinfunction "DRVP_A1") (pintype "bidirectional"))
    )
    (net (code "42") (name "Net-(U$30-RBIAS)") (class "Default")
      (node (ref "R44") (pin "1") (pinfunction "1_1") (pintype "passive"))
      (node (ref "U$30") (pin "B2") (pinfunction "RBIAS_B2") (pintype "bidirectional"))
    )
    (net (code "43") (name "Net-(U$30-VBG)") (class "Default")
      (node (ref "C34") (pin "1") (pinfunction "1_1") (pintype "passive"))
      (node (ref "U$30") (pin "B1") (pinfunction "VBG_B1") (pintype "bidirectional"))
    )
    (net (code "44") (name "Net-(U$30-VREF)") (class "Default")
      (node (ref "C32") (pin "1") (pinfunction "1_1") (pintype "passive"))
      (node (ref "U$30") (pin "D1") (pinfunction "VREF_D1") (pintype "bidirectional"))
    )
    (net (code "45") (name "Net-(U$32-1)") (class "Default")
      (node (ref "C17") (pin "1") (pinfunction "1_1") (pintype "passive"))
      (node (ref "U$32") (pin "P$1") (pinfunction "1_P$1") (pintype "passive"))
      (node (ref "U4") (pin "9") (pinfunction "32KOUT_9") (pintype "output"))
    )
    (net (code "46") (name "Net-(U$32-2)") (class "Default")
      (node (ref "C18") (pin "2") (pinfunction "2_2") (pintype "passive"))
      (node (ref "U$32") (pin "P$2") (pinfunction "2_P$2") (pintype "passive"))
      (node (ref "U4") (pin "8") (pinfunction "32KIN_8") (pintype "input"))
    )
    (net (code "47") (name "Net-(U1-LX)") (class "Default")
      (node (ref "L1") (pin "2") (pinfunction "2_2") (pintype "passive"))
      (node (ref "U1") (pin "2") (pinfunction "LX_2") (pintype "bidirectional"))
    )
    (net (code "48") (name "Net-(U1-SEL)") (class "Default")
      (node (ref "R14") (pin "2") (pinfunction "2_2") (pintype "passive"))
      (node (ref "U1") (pin "4") (pinfunction "SEL_4") (pintype "bidirectional"))
    )
    (net (code "49") (name "Net-(U4-P0.3)") (class "Default")
      (node (ref "R21") (pin "1") (pinfunction "1_1") (pintype "passive"))
      (node (ref "U4") (pin "38") (pinfunction "P0.3_38") (pintype "input"))
    )
    (net (code "50") (name "Net-(U4-PD2_CAT)") (class "Default")
      (node (ref "U4") (pin "25") (pinfunction "PD2_IN_25") (pintype "input"))
      (node (ref "U4") (pin "26") (pinfunction "PD2_CAT_26") (pintype "passive"))
    )
    (net (code "51") (name "Net-(U4-VCORE)") (class "Default")
      (node (ref "C28") (pin "1") (pinfunction "1_1") (pintype "passive"))
      (node (ref "U4") (pin "5") (pinfunction "VCORE_5") (pintype "power_in"))
    )
    (net (code "52") (name "Net-(U4-VREF)") (class "Default")
      (node (ref "C37") (pin "2") (pinfunction "2_2") (pintype "passive"))
      (node (ref "U4") (pin "2") (pinfunction "VREF_2") (pintype "passive"))
    )
    (net (code "53") (name "Net-(U6-NO2)") (class "Default")
      (node (ref "D3") (pin "C1") (pinfunction "C_C1") (pintype "passive"))
      (node (ref "D3") (pin "C2") (pinfunction "C_C2") (pintype "passive"))
      (node (ref "U6") (pin "15") (pinfunction "NO2_15") (pintype "bidirectional"))
    )
    (net (code "54") (name "Net-(U9-OUT)") (class "Default")
      (node (ref "C11") (pin "1") (pinfunction "1_1") (pintype "passive"))
      (node (ref "R23") (pin "2") (pinfunction "2_2") (pintype "passive"))
      (node (ref "U9") (pin "5") (pinfunction "OUT_5") (pintype "passive"))
    )
    (net (code "55") (name "RESET") (class "Default")
      (node (ref "C7") (pin "1") (pinfunction "1_1") (pintype "passive"))
      (node (ref "J1") (pin "1") (pinfunction "1_1") (pintype "passive"))
      (node (ref "R1") (pin "1") (pinfunction "1_1") (pintype "passive"))
      (node (ref "SWIO8") (pin "TP") (pinfunction "TP_TP") (pintype "input"))
      (node (ref "U$3") (pin "6") (pinfunction "RSTN_6") (pintype "bidirectional"))
    )
    (net (code "56") (name "RESET_1") (class "Default")
      (node (ref "C36") (pin "1") (pinfunction "1_1") (pintype "passive"))
      (node (ref "J1") (pin "2") (pinfunction "2_2") (pintype "passive"))
      (node (ref "R1") (pin "2") (pinfunction "2_2") (pintype "passive"))
      (node (ref "U4") (pin "10") (pinfunction "RSTN_10") (pintype "input"))
    )
    (net (code "57") (name "SCK") (class "Default")
      (node (ref "J1") (pin "18") (pinfunction "18_18") (pintype "passive"))
      (node (ref "SWIO4") (pin "TP") (pinfunction "TP_TP") (pintype "input"))
      (node (ref "U$30") (pin "E5") (pinfunction "SCLK_E5") (pintype "bidirectional"))
    )
    (net (code "58") (name "SCL") (class "Default")
      (node (ref "J1") (pin "4") (pinfunction "4_4") (pintype "passive"))
      (node (ref "R13") (pin "2") (pinfunction "2_2") (pintype "passive"))
      (node (ref "R3") (pin "2") (pinfunction "2_2") (pintype "passive"))
      (node (ref "U$3") (pin "24") (pinfunction "SLAVE_SCL_24") (pintype "bidirectional"))
      (node (ref "U4") (pin "3") (pinfunction "P0.8_3") (pintype "passive"))
    )
    (net (code "59") (name "SDA") (class "Default")
      (node (ref "J1") (pin "3") (pinfunction "3_3") (pintype "passive"))
      (node (ref "R16") (pin "2") (pinfunction "2_2") (pintype "passive"))
      (node (ref "R4") (pin "2") (pinfunction "2_2") (pintype "passive"))
      (node (ref "U$3") (pin "23") (pinfunction "SLAVE_SDA_23") (pintype "bidirectional"))
      (node (ref "U4") (pin "4") (pinfunction "P0.9_4") (pintype "passive"))
    )
    (net (code "60") (name "SDI") (class "Default")
      (node (ref "U$39") (pin "2") (pinfunction "SDI/SDA_2") (pintype "bidirectional"))
      (node (ref "U4") (pin "36") (pinfunction "P0.5_36") (pintype "bidirectional"))
    )
    (net (code "61") (name "SDO") (class "Default")
      (node (ref "U$39") (pin "1") (pinfunction "SDO/ADDR_1") (pintype "bidirectional"))
      (node (ref "U4") (pin "37") (pinfunction "P0.4_37") (pintype "bidirectional"))
    )
    (net (code "62") (name "SEN_CS") (class "Default")
      (node (ref "U$39") (pin "10") (pinfunction "NCS_10") (pintype "bidirectional"))
      (node (ref "U4") (pin "11") (pinfunction "P0.0_11") (pintype "passive"))
    )
    (net (code "63") (name "SEN_SCK") (class "Default")
      (node (ref "U$39") (pin "12") (pinfunction "SCLK/SCL_12") (pintype "bidirectional"))
      (node (ref "U4") (pin "35") (pinfunction "P0.6_35") (pintype "bidirectional"))
    )
    (net (code "64") (name "S_SCL") (class "Default")
      (node (ref "D2") (pin "2") (pinfunction "2_2") (pintype "bidirectional"))
      (node (ref "J2") (pin "16") (pinfunction "16_16") (pintype "passive"))
      (node (ref "JP1") (pin "4") (pinfunction "P$4_4") (pintype "bidirectional"))
      (node (ref "R5") (pin "2") (pinfunction "2_2") (pintype "passive"))
      (node (ref "U$3") (pin "14") (pinfunction "SENSOR_SCL_14") (pintype "bidirectional"))
    )
    (net (code "65") (name "S_SDA") (class "Default")
      (node (ref "D1") (pin "2") (pinfunction "2_2") (pintype "bidirectional"))
      (node (ref "J2") (pin "18") (pinfunction "18_18") (pintype "passive"))
      (node (ref "JP1") (pin "3") (pinfunction "P$3_3") (pintype "bidirectional"))
      (node (ref "R6") (pin "2") (pinfunction "2_2") (pintype "passive"))
      (node (ref "U$3") (pin "13") (pinfunction "SENSOR_SDA_13") (pintype "bidirectional"))
    )
    (net (code "66") (name "VBAT") (class "Default")
      (node (ref "C10") (pin "1") (pinfunction "1_1") (pintype "passive"))
      (node (ref "C12") (pin "1") (pinfunction "1_1") (pintype "passive"))
      (node (ref "C19") (pin "1") (pinfunction "1_1") (pintype "passive"))
      (node (ref "J2") (pin "11") (pinfunction "11_11") (pintype "passive"))
      (node (ref "J2") (pin "13") (pinfunction "13_13") (pintype "passive"))
      (node (ref "J2") (pin "15") (pinfunction "15_15") (pintype "passive"))
      (node (ref "L1") (pin "1") (pinfunction "1_1") (pintype "passive"))
      (node (ref "U$6") (pin "1") (pinfunction "VIN_1") (pintype "bidirectional"))
      (node (ref "U$6") (pin "3") (pinfunction "EN_3") (pintype "bidirectional"))
      (node (ref "U1") (pin "5") (pinfunction "IN_5") (pintype "input"))
      (node (ref "U1") (pin "6") (pinfunction "EN_6") (pintype "bidirectional"))
      (node (ref "U9") (pin "1") (pinfunction "IN_1") (pintype "input"))
      (node (ref "U9") (pin "3") (pinfunction "EN_3") (pintype "input"))
    )
    (net (code "67") (name "VSENSE") (class "Default")
      (node (ref "C27") (pin "1") (pinfunction "1_1") (pintype "passive"))
      (node (ref "C38") (pin "1") (pinfunction "1_1") (pintype "passive"))
      (node (ref "C39") (pin "1") (pinfunction "1_1") (pintype "passive"))
      (node (ref "C40") (pin "1") (pinfunction "1_1") (pintype "passive"))
      (node (ref "C41") (pin "1") (pinfunction "1_1") (pintype "passive"))
      (node (ref "C42") (pin "1") (pinfunction "1_1") (pintype "passive"))
      (node (ref "C48") (pin "1") (pinfunction "1_1") (pintype "passive"))
      (node (ref "C9") (pin "1") (pinfunction "1_1") (pintype "passive"))
      (node (ref "D3") (pin "A") (pinfunction "A_A") (pintype "passive"))
      (node (ref "D4") (pin "A") (pinfunction "A_A") (pintype "passive"))
      (node (ref "J2") (pin "17") (pinfunction "17_17") (pintype "passive"))
      (node (ref "J2") (pin "19") (pinfunction "19_19") (pintype "passive"))
      (node (ref "JP1") (pin "1") (pinfunction "P$1_1") (pintype "bidirectional"))
      (node (ref "LED1") (pin "3") (pinfunction "A_3") (pintype "passive"))
      (node (ref "U1") (pin "1") (pinfunction "OUT_1") (pintype "output"))
      (node (ref "U4") (pin "18") (pinfunction "VLED_18") (pintype "input"))
      (node (ref "U6") (pin "10") (pinfunction "V+_10") (pintype "power_in"))
    )
    (net (code "68") (name "W_MFIO") (class "Default")
      (node (ref "J1") (pin "10") (pinfunction "10_10") (pintype "passive"))
      (node (ref "R2") (pin "1") (pinfunction "1_1") (pintype "passive"))
      (node (ref "SWIO9") (pin "TP") (pinfunction "TP_TP") (pintype "input"))
      (node (ref "U4") (pin "12") (pinfunction "P0.1_12") (pintype "passive"))
    )
    (net (code "69") (name "unconnected-(J1-Pad7)") (class "Default")
      (node (ref "J1") (pin "7") (pinfunction "7_7") (pintype "passive"))
    )
    (net (code "70") (name "unconnected-(J1-Pad12)") (class "Default")
      (node (ref "J1") (pin "12") (pinfunction "12_12") (pintype "passive"))
    )
    (net (code "71") (name "unconnected-(J1-Pad13)") (class "Default")
      (node (ref "J1") (pin "13") (pinfunction "13_13") (pintype "passive"))
    )
    (net (code "72") (name "unconnected-(J1-Pad16)") (class "Default")
      (node (ref "J1") (pin "16") (pinfunction "16_16") (pintype "passive"))
    )
    (net (code "73") (name "unconnected-(J2-Pad7)") (class "Default")
      (node (ref "J2") (pin "7") (pinfunction "7_7") (pintype "passive"))
    )
    (net (code "74") (name "unconnected-(J2-Pad8)") (class "Default")
      (node (ref "J2") (pin "8") (pinfunction "8_8") (pintype "passive"))
    )
    (net (code "75") (name "unconnected-(J2-Pad9)") (class "Default")
      (node (ref "J2") (pin "9") (pinfunction "9_9") (pintype "passive"))
    )
    (net (code "76") (name "unconnected-(J2-Pad10)") (class "Default")
      (node (ref "J2") (pin "10") (pinfunction "10_10") (pintype "passive"))
    )
    (net (code "77") (name "unconnected-(J2-Pad12)") (class "Default")
      (node (ref "J2") (pin "12") (pinfunction "12_12") (pintype "passive"))
    )
    (net (code "78") (name "unconnected-(U$3-ACCL_INT-Pad19)") (class "Default")
      (node (ref "U$3") (pin "19") (pinfunction "ACCL_INT_19") (pintype "bidirectional"))
    )
    (net (code "79") (name "unconnected-(U$3-D.N.C-Pad2)") (class "Default")
      (node (ref "U$3") (pin "2") (pinfunction "D.N.C_2") (pintype "bidirectional"))
    )
    (net (code "80") (name "unconnected-(U$3-D.N.C-Pad4)") (class "Default")
      (node (ref "U$3") (pin "4") (pinfunction "D.N.C_4") (pintype "bidirectional"))
    )
    (net (code "81") (name "unconnected-(U$3-D.N.C-Pad5)") (class "Default")
      (node (ref "U$3") (pin "5") (pinfunction "D.N.C_5") (pintype "bidirectional"))
    )
    (net (code "82") (name "unconnected-(U$3-D.N.C-Pad16)") (class "Default")
      (node (ref "U$3") (pin "16") (pinfunction "D.N.C_16") (pintype "bidirectional"))
    )
    (net (code "83") (name "unconnected-(U$3-D.N.C-Pad17)") (class "Default")
      (node (ref "U$3") (pin "17") (pinfunction "D.N.C_17") (pintype "bidirectional"))
    )
    (net (code "84") (name "unconnected-(U$3-D.N.C-Pad20)") (class "Default")
      (node (ref "U$3") (pin "20") (pinfunction "D.N.C_20") (pintype "bidirectional"))
    )
    (net (code "85") (name "unconnected-(U$3-D.N.C-Pad21)") (class "Default")
      (node (ref "U$3") (pin "21") (pinfunction "D.N.C_21") (pintype "bidirectional"))
    )
    (net (code "86") (name "unconnected-(U$3-N.C-Pad3)") (class "Default")
      (node (ref "U$3") (pin "3") (pinfunction "N.C_3") (pintype "bidirectional"))
    )
    (net (code "87") (name "unconnected-(U$3-N.C-Pad15)") (class "Default")
      (node (ref "U$3") (pin "15") (pinfunction "N.C_15") (pintype "bidirectional"))
    )
    (net (code "88") (name "unconnected-(U$6-NC-Pad4)") (class "Default")
      (node (ref "U$6") (pin "4") (pinfunction "NC_4") (pintype "bidirectional"))
    )
    (net (code "89") (name "unconnected-(U$29-NC-Pad1)") (class "Default")
      (node (ref "U$29") (pin "1") (pinfunction "NC_1") (pintype "bidirectional"))
    )
    (net (code "90") (name "unconnected-(U$30-AOUT-PadC2)") (class "Default")
      (node (ref "U$30") (pin "C2") (pinfunction "AOUT_C2") (pintype "bidirectional"))
    )
    (net (code "91") (name "unconnected-(U$30-INT2B-PadE2)") (class "Default")
      (node (ref "U$30") (pin "E2") (pinfunction "INT2B_E2") (pintype "bidirectional"))
    )
    (net (code "92") (name "unconnected-(U$39-INT2-Pad6)") (class "Default")
      (node (ref "U$39") (pin "6") (pinfunction "INT2_6") (pintype "bidirectional"))
    )
    (net (code "93") (name "unconnected-(U$39-NC-Pad11)") (class "Default")
      (node (ref "U$39") (pin "11") (pinfunction "NC_11") (pintype "bidirectional"))
    )
    (net (code "94") (name "unconnected-(U4-NC-Pad34)") (class "Default")
      (node (ref "U4") (pin "34") (pinfunction "NC_34") (pintype "passive"))
    )
    (net (code "95") (name "unconnected-(U4-NC_2-Pad14)") (class "Default")
      (node (ref "U4") (pin "14") (pinfunction "NC_2_14") (pintype "passive"))
    )
    (net (code "96") (name "unconnected-(U4-NC_3-Pad15)") (class "Default")
      (node (ref "U4") (pin "15") (pinfunction "NC_3_15") (pintype "passive"))
    )
    (net (code "97") (name "unconnected-(U4-NC_4-Pad16)") (class "Default")
      (node (ref "U4") (pin "16") (pinfunction "NC_4_16") (pintype "passive"))
    )
    (net (code "98") (name "unconnected-(U4-NC_5-Pad17)") (class "Default")
      (node (ref "U4") (pin "17") (pinfunction "NC_5_17") (pintype "passive"))
    )
    (net (code "99") (name "unconnected-(U4-NC_6-Pad27)") (class "Default")
      (node (ref "U4") (pin "27") (pinfunction "NC_6_27") (pintype "passive"))
    )
    (net (code "100") (name "unconnected-(U4-PD1_IN-Pad1)") (class "Default")
      (node (ref "U4") (pin "1") (pinfunction "PD1_IN_1") (pintype "input"))
    )
    (net (code "101") (name "unconnected-(U6-COM3-Pad4)") (class "Default")
      (node (ref "U6") (pin "4") (pinfunction "COM3_4") (pintype "bidirectional"))
    )
    (net (code "102") (name "unconnected-(U6-COM4-Pad8)") (class "Default")
      (node (ref "U6") (pin "8") (pinfunction "COM4_8") (pintype "bidirectional"))
    )
    (net (code "103") (name "unconnected-(U6-NC3-Pad5)") (class "Default")
      (node (ref "U6") (pin "5") (pinfunction "NC3_5") (pintype "bidirectional"))
    )
    (net (code "104") (name "unconnected-(U6-NC4-Pad9)") (class "Default")
      (node (ref "U6") (pin "9") (pinfunction "NC4_9") (pintype "bidirectional"))
    )
    (net (code "105") (name "unconnected-(U6-NO3-Pad3)") (class "Default")
      (node (ref "U6") (pin "3") (pinfunction "NO3_3") (pintype "bidirectional"))
    )
    (net (code "106") (name "unconnected-(U6-NO4-Pad7)") (class "Default")
      (node (ref "U6") (pin "7") (pinfunction "NO4_7") (pintype "bidirectional"))
    )
    (net (code "107") (name "unconnected-(U9-BP-Pad4)") (class "Default")
      (node (ref "U9") (pin "4") (pinfunction "BP_4") (pintype "input"))
    )
  )
)
